# TopLevelBoard.net
KiCad netlist of a schematic drawn in Altium Designer
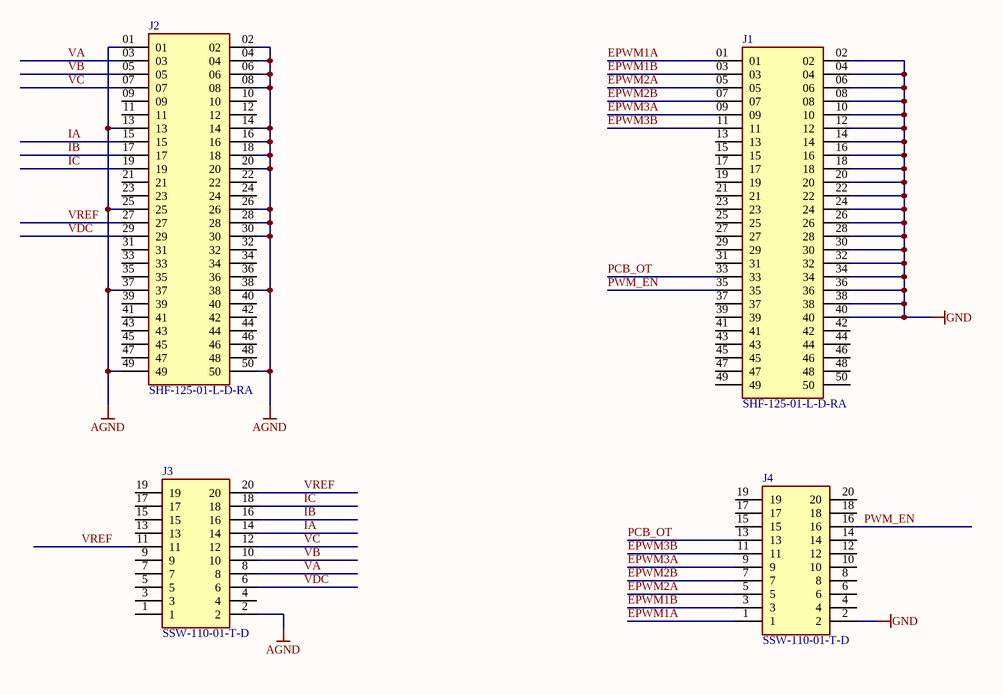
[diagram p0: TopLevelBoard.SchDoc]

(export (version "E")
  (design (tool "Eeschema 10.0.6"))
  (components
    (comp (ref "J1")
      (value "SHF-125-01-L-D-RA")
      (footprint "SAMTEC_SHF-125-01-L-D-RA")
      (fields (field (name "MF") "Samtec"))
      (libsource (lib "FYP_Connectors") (part "SHF-125-01-L-D-RA"))
    )
    (comp (ref "J2")
      (value "SHF-125-01-L-D-RA")
      (footprint "SAMTEC_SHF-125-01-L-D-RA")
      (fields (field (name "MF") "Samtec"))
      (libsource (lib "FYP_Connectors") (part "SHF-125-01-L-D-RA"))
    )
    (comp (ref "J3")
      (value "SSW-110-01-T-D")
      (footprint "SAMTEC_SSW-110-01-T-D")
      (description "Connector")
      (fields (field (name "MOUSER PART NUMBER") "200-SSW11001TD"))
      (libsource (lib "FYP_Connectors") (part "SSW-110-01-T-D"))
    )
    (comp (ref "J4")
      (value "SSW-110-01-T-D")
      (footprint "SAMTEC_SSW-110-01-T-D")
      (description "Connector")
      (fields (field (name "MOUSER PART NUMBER") "200-SSW11001TD"))
      (libsource (lib "FYP_Connectors") (part "SSW-110-01-T-D"))
    )
  )
  (nets
    (net (code "1") (name "/EPWM1A") (class "Default")
      (node (ref "J1") (pin "01") (pinfunction "01_01") (pintype "passive"))
      (node (ref "J4") (pin "1") (pinfunction "1_1") (pintype "passive"))
    )
    (net (code "2") (name "/EPWM1B") (class "Default")
      (node (ref "J1") (pin "03") (pinfunction "03_03") (pintype "passive"))
      (node (ref "J4") (pin "3") (pinfunction "3_3") (pintype "passive"))
    )
    (net (code "3") (name "/EPWM2A") (class "Default")
      (node (ref "J1") (pin "05") (pinfunction "05_05") (pintype "passive"))
      (node (ref "J4") (pin "5") (pinfunction "5_5") (pintype "passive"))
    )
    (net (code "4") (name "/EPWM2B") (class "Default")
      (node (ref "J1") (pin "07") (pinfunction "07_07") (pintype "passive"))
      (node (ref "J4") (pin "7") (pinfunction "7_7") (pintype "passive"))
    )
    (net (code "5") (name "/EPWM3A") (class "Default")
      (node (ref "J1") (pin "09") (pinfunction "09_09") (pintype "passive"))
      (node (ref "J4") (pin "9") (pinfunction "9_9") (pintype "passive"))
    )
    (net (code "6") (name "/EPWM3B") (class "Default")
      (node (ref "J1") (pin "11") (pinfunction "11_11") (pintype "passive"))
      (node (ref "J4") (pin "11") (pinfunction "11_11") (pintype "passive"))
    )
    (net (code "7") (name "/IA") (class "Default")
      (node (ref "J2") (pin "15") (pinfunction "15_15") (pintype "passive"))
      (node (ref "J3") (pin "14") (pinfunction "14_14") (pintype "passive"))
    )
    (net (code "8") (name "/IB") (class "Default")
      (node (ref "J2") (pin "17") (pinfunction "17_17") (pintype "passive"))
      (node (ref "J3") (pin "16") (pinfunction "16_16") (pintype "passive"))
    )
    (net (code "9") (name "/IC") (class "Default")
      (node (ref "J2") (pin "19") (pinfunction "19_19") (pintype "passive"))
      (node (ref "J3") (pin "18") (pinfunction "18_18") (pintype "passive"))
    )
    (net (code "10") (name "/PCB_OT") (class "Default")
      (node (ref "J1") (pin "33") (pinfunction "33_33") (pintype "passive"))
      (node (ref "J4") (pin "13") (pinfunction "13_13") (pintype "passive"))
    )
    (net (code "11") (name "/PWM_EN") (class "Default")
      (node (ref "J1") (pin "35") (pinfunction "35_35") (pintype "passive"))
      (node (ref "J4") (pin "16") (pinfunction "16_16") (pintype "passive"))
    )
    (net (code "12") (name "/VA") (class "Default")
      (node (ref "J2") (pin "03") (pinfunction "03_03") (pintype "passive"))
      (node (ref "J3") (pin "8") (pinfunction "8_8") (pintype "passive"))
    )
    (net (code "13") (name "/VB") (class "Default")
      (node (ref "J2") (pin "05") (pinfunction "05_05") (pintype "passive"))
      (node (ref "J3") (pin "10") (pinfunction "10_10") (pintype "passive"))
    )
    (net (code "14") (name "/VC") (class "Default")
      (node (ref "J2") (pin "07") (pinfunction "07_07") (pintype "passive"))
      (node (ref "J3") (pin "12") (pinfunction "12_12") (pintype "passive"))
    )
    (net (code "15") (name "/VDC") (class "Default")
      (node (ref "J2") (pin "29") (pinfunction "29_29") (pintype "passive"))
      (node (ref "J3") (pin "6") (pinfunction "6_6") (pintype "passive"))
    )
    (net (code "16") (name "/VREF") (class "Default")
      (node (ref "J2") (pin "27") (pinfunction "27_27") (pintype "passive"))
      (node (ref "J3") (pin "11") (pinfunction "11_11") (pintype "passive"))
      (node (ref "J3") (pin "20") (pinfunction "20_20") (pintype "passive"))
    )
    (net (code "17") (name "AGND") (class "Default")
      (node (ref "J2") (pin "01") (pinfunction "01_01") (pintype "passive"))
      (node (ref "J2") (pin "02") (pinfunction "02_02") (pintype "passive"))
      (node (ref "J2") (pin "04") (pinfunction "04_04") (pintype "passive"))
      (node (ref "J2") (pin "06") (pinfunction "06_06") (pintype "passive"))
      (node (ref "J2") (pin "08") (pinfunction "08_08") (pintype "passive"))
      (node (ref "J2") (pin "13") (pinfunction "13_13") (pintype "passive"))
      (node (ref "J2") (pin "14") (pinfunction "14_14") (pintype "passive"))
      (node (ref "J2") (pin "16") (pinfunction "16_16") (pintype "passive"))
      (node (ref "J2") (pin "18") (pinfunction "18_18") (pintype "passive"))
      (node (ref "J2") (pin "20") (pinfunction "20_20") (pintype "passive"))
      (node (ref "J2") (pin "25") (pinfunction "25_25") (pintype "passive"))
      (node (ref "J2") (pin "26") (pinfunction "26_26") (pintype "passive"))
      (node (ref "J2") (pin "28") (pinfunction "28_28") (pintype "passive"))
      (node (ref "J2") (pin "30") (pinfunction "30_30") (pintype "passive"))
      (node (ref "J2") (pin "37") (pinfunction "37_37") (pintype "passive"))
      (node (ref "J2") (pin "38") (pinfunction "38_38") (pintype "passive"))
      (node (ref "J2") (pin "49") (pinfunction "49_49") (pintype "passive"))
      (node (ref "J2") (pin "50") (pinfunction "50_50") (pintype "passive"))
      (node (ref "J3") (pin "2") (pinfunction "2_2") (pintype "passive"))
    )
    (net (code "18") (name "GND") (class "Default")
      (node (ref "J1") (pin "02") (pinfunction "02_02") (pintype "passive"))
      (node (ref "J1") (pin "04") (pinfunction "04_04") (pintype "passive"))
      (node (ref "J1") (pin "06") (pinfunction "06_06") (pintype "passive"))
      (node (ref "J1") (pin "08") (pinfunction "08_08") (pintype "passive"))
      (node (ref "J1") (pin "10") (pinfunction "10_10") (pintype "passive"))
      (node (ref "J1") (pin "12") (pinfunction "12_12") (pintype "passive"))
      (node (ref "J1") (pin "14") (pinfunction "14_14") (pintype "passive"))
      (node (ref "J1") (pin "16") (pinfunction "16_16") (pintype "passive"))
      (node (ref "J1") (pin "18") (pinfunction "18_18") (pintype "passive"))
      (node (ref "J1") (pin "20") (pinfunction "20_20") (pintype "passive"))
      (node (ref "J1") (pin "22") (pinfunction "22_22") (pintype "passive"))
      (node (ref "J1") (pin "24") (pinfunction "24_24") (pintype "passive"))
      (node (ref "J1") (pin "26") (pinfunction "26_26") (pintype "passive"))
      (node (ref "J1") (pin "28") (pinfunction "28_28") (pintype "passive"))
      (node (ref "J1") (pin "30") (pinfunction "30_30") (pintype "passive"))
      (node (ref "J1") (pin "32") (pinfunction "32_32") (pintype "passive"))
      (node (ref "J1") (pin "34") (pinfunction "34_34") (pintype "passive"))
      (node (ref "J1") (pin "36") (pinfunction "36_36") (pintype "passive"))
      (node (ref "J1") (pin "38") (pinfunction "38_38") (pintype "passive"))
      (node (ref "J1") (pin "40") (pinfunction "40_40") (pintype "passive"))
      (node (ref "J4") (pin "2") (pinfunction "2_2") (pintype "passive"))
    )
    (net (code "19") (name "unconnected-(J1-Pad13)") (class "Default")
      (node (ref "J1") (pin "13") (pinfunction "13_13") (pintype "passive"))
    )
    (net (code "20") (name "unconnected-(J1-Pad15)") (class "Default")
      (node (ref "J1") (pin "15") (pinfunction "15_15") (pintype "passive"))
    )
    (net (code "21") (name "unconnected-(J1-Pad17)") (class "Default")
      (node (ref "J1") (pin "17") (pinfunction "17_17") (pintype "passive"))
    )
    (net (code "22") (name "unconnected-(J1-Pad19)") (class "Default")
      (node (ref "J1") (pin "19") (pinfunction "19_19") (pintype "passive"))
    )
    (net (code "23") (name "unconnected-(J1-Pad21)") (class "Default")
      (node (ref "J1") (pin "21") (pinfunction "21_21") (pintype "passive"))
    )
    (net (code "24") (name "unconnected-(J1-Pad23)") (class "Default")
      (node (ref "J1") (pin "23") (pinfunction "23_23") (pintype "passive"))
    )
    (net (code "25") (name "unconnected-(J1-Pad25)") (class "Default")
      (node (ref "J1") (pin "25") (pinfunction "25_25") (pintype "passive"))
    )
    (net (code "26") (name "unconnected-(J1-Pad27)") (class "Default")
      (node (ref "J1") (pin "27") (pinfunction "27_27") (pintype "passive"))
    )
    (net (code "27") (name "unconnected-(J1-Pad29)") (class "Default")
      (node (ref "J1") (pin "29") (pinfunction "29_29") (pintype "passive"))
    )
    (net (code "28") (name "unconnected-(J1-Pad31)") (class "Default")
      (node (ref "J1") (pin "31") (pinfunction "31_31") (pintype "passive"))
    )
    (net (code "29") (name "unconnected-(J1-Pad37)") (class "Default")
      (node (ref "J1") (pin "37") (pinfunction "37_37") (pintype "passive"))
    )
    (net (code "30") (name "unconnected-(J1-Pad39)") (class "Default")
      (node (ref "J1") (pin "39") (pinfunction "39_39") (pintype "passive"))
    )
    (net (code "31") (name "unconnected-(J1-Pad41)") (class "Default")
      (node (ref "J1") (pin "41") (pinfunction "41_41") (pintype "passive"))
    )
    (net (code "32") (name "unconnected-(J1-Pad42)") (class "Default")
      (node (ref "J1") (pin "42") (pinfunction "42_42") (pintype "passive"))
    )
    (net (code "33") (name "unconnected-(J1-Pad43)") (class "Default")
      (node (ref "J1") (pin "43") (pinfunction "43_43") (pintype "passive"))
    )
    (net (code "34") (name "unconnected-(J1-Pad44)") (class "Default")
      (node (ref "J1") (pin "44") (pinfunction "44_44") (pintype "passive"))
    )
    (net (code "35") (name "unconnected-(J1-Pad45)") (class "Default")
      (node (ref "J1") (pin "45") (pinfunction "45_45") (pintype "passive"))
    )
    (net (code "36") (name "unconnected-(J1-Pad46)") (class "Default")
      (node (ref "J1") (pin "46") (pinfunction "46_46") (pintype "passive"))
    )
    (net (code "37") (name "unconnected-(J1-Pad47)") (class "Default")
      (node (ref "J1") (pin "47") (pinfunction "47_47") (pintype "passive"))
    )
    (net (code "38") (name "unconnected-(J1-Pad48)") (class "Default")
      (node (ref "J1") (pin "48") (pinfunction "48_48") (pintype "passive"))
    )
    (net (code "39") (name "unconnected-(J1-Pad49)") (class "Default")
      (node (ref "J1") (pin "49") (pinfunction "49_49") (pintype "passive"))
    )
    (net (code "40") (name "unconnected-(J1-Pad50)") (class "Default")
      (node (ref "J1") (pin "50") (pinfunction "50_50") (pintype "passive"))
    )
    (net (code "41") (name "unconnected-(J2-Pad09)") (class "Default")
      (node (ref "J2") (pin "09") (pinfunction "09_09") (pintype "passive"))
    )
    (net (code "42") (name "unconnected-(J2-Pad10)") (class "Default")
      (node (ref "J2") (pin "10") (pinfunction "10_10") (pintype "passive"))
    )
    (net (code "43") (name "unconnected-(J2-Pad11)") (class "Default")
      (node (ref "J2") (pin "11") (pinfunction "11_11") (pintype "passive"))
    )
    (net (code "44") (name "unconnected-(J2-Pad12)") (class "Default")
      (node (ref "J2") (pin "12") (pinfunction "12_12") (pintype "passive"))
    )
    (net (code "45") (name "unconnected-(J2-Pad21)") (class "Default")
      (node (ref "J2") (pin "21") (pinfunction "21_21") (pintype "passive"))
    )
    (net (code "46") (name "unconnected-(J2-Pad22)") (class "Default")
      (node (ref "J2") (pin "22") (pinfunction "22_22") (pintype "passive"))
    )
    (net (code "47") (name "unconnected-(J2-Pad23)") (class "Default")
      (node (ref "J2") (pin "23") (pinfunction "23_23") (pintype "passive"))
    )
    (net (code "48") (name "unconnected-(J2-Pad24)") (class "Default")
      (node (ref "J2") (pin "24") (pinfunction "24_24") (pintype "passive"))
    )
    (net (code "49") (name "unconnected-(J2-Pad31)") (class "Default")
      (node (ref "J2") (pin "31") (pinfunction "31_31") (pintype "passive"))
    )
    (net (code "50") (name "unconnected-(J2-Pad32)") (class "Default")
      (node (ref "J2") (pin "32") (pinfunction "32_32") (pintype "passive"))
    )
    (net (code "51") (name "unconnected-(J2-Pad33)") (class "Default")
      (node (ref "J2") (pin "33") (pinfunction "33_33") (pintype "passive"))
    )
    (net (code "52") (name "unconnected-(J2-Pad34)") (class "Default")
      (node (ref "J2") (pin "34") (pinfunction "34_34") (pintype "passive"))
    )
    (net (code "53") (name "unconnected-(J2-Pad35)") (class "Default")
      (node (ref "J2") (pin "35") (pinfunction "35_35") (pintype "passive"))
    )
    (net (code "54") (name "unconnected-(J2-Pad36)") (class "Default")
      (node (ref "J2") (pin "36") (pinfunction "36_36") (pintype "passive"))
    )
    (net (code "55") (name "unconnected-(J2-Pad39)") (class "Default")
      (node (ref "J2") (pin "39") (pinfunction "39_39") (pintype "passive"))
    )
    (net (code "56") (name "unconnected-(J2-Pad40)") (class "Default")
      (node (ref "J2") (pin "40") (pinfunction "40_40") (pintype "passive"))
    )
    (net (code "57") (name "unconnected-(J2-Pad41)") (class "Default")
      (node (ref "J2") (pin "41") (pinfunction "41_41") (pintype "passive"))
    )
    (net (code "58") (name "unconnected-(J2-Pad42)") (class "Default")
      (node (ref "J2") (pin "42") (pinfunction "42_42") (pintype "passive"))
    )
    (net (code "59") (name "unconnected-(J2-Pad43)") (class "Default")
      (node (ref "J2") (pin "43") (pinfunction "43_43") (pintype "passive"))
    )
    (net (code "60") (name "unconnected-(J2-Pad44)") (class "Default")
      (node (ref "J2") (pin "44") (pinfunction "44_44") (pintype "passive"))
    )
    (net (code "61") (name "unconnected-(J2-Pad45)") (class "Default")
      (node (ref "J2") (pin "45") (pinfunction "45_45") (pintype "passive"))
    )
    (net (code "62") (name "unconnected-(J2-Pad46)") (class "Default")
      (node (ref "J2") (pin "46") (pinfunction "46_46") (pintype "passive"))
    )
    (net (code "63") (name "unconnected-(J2-Pad47)") (class "Default")
      (node (ref "J2") (pin "47") (pinfunction "47_47") (pintype "passive"))
    )
    (net (code "64") (name "unconnected-(J2-Pad48)") (class "Default")
      (node (ref "J2") (pin "48") (pinfunction "48_48") (pintype "passive"))
    )
    (net (code "65") (name "unconnected-(J3-Pad1)") (class "Default")
      (node (ref "J3") (pin "1") (pinfunction "1_1") (pintype "passive"))
    )
    (net (code "66") (name "unconnected-(J3-Pad3)") (class "Default")
      (node (ref "J3") (pin "3") (pinfunction "3_3") (pintype "passive"))
    )
    (net (code "67") (name "unconnected-(J3-Pad4)") (class "Default")
      (node (ref "J3") (pin "4") (pinfunction "4_4") (pintype "passive"))
    )
    (net (code "68") (name "unconnected-(J3-Pad5)") (class "Default")
      (node (ref "J3") (pin "5") (pinfunction "5_5") (pintype "passive"))
    )
    (net (code "69") (name "unconnected-(J3-Pad7)") (class "Default")
      (node (ref "J3") (pin "7") (pinfunction "7_7") (pintype "passive"))
    )
    (net (code "70") (name "unconnected-(J3-Pad9)") (class "Default")
      (node (ref "J3") (pin "9") (pinfunction "9_9") (pintype "passive"))
    )
    (net (code "71") (name "unconnected-(J3-Pad13)") (class "Default")
      (node (ref "J3") (pin "13") (pinfunction "13_13") (pintype "passive"))
    )
    (net (code "72") (name "unconnected-(J3-Pad15)") (class "Default")
      (node (ref "J3") (pin "15") (pinfunction "15_15") (pintype "passive"))
    )
    (net (code "73") (name "unconnected-(J3-Pad17)") (class "Default")
      (node (ref "J3") (pin "17") (pinfunction "17_17") (pintype "passive"))
    )
    (net (code "74") (name "unconnected-(J3-Pad19)") (class "Default")
      (node (ref "J3") (pin "19") (pinfunction "19_19") (pintype "passive"))
    )
    (net (code "75") (name "unconnected-(J4-Pad4)") (class "Default")
      (node (ref "J4") (pin "4") (pinfunction "4_4") (pintype "passive"))
    )
    (net (code "76") (name "unconnected-(J4-Pad6)") (class "Default")
      (node (ref "J4") (pin "6") (pinfunction "6_6") (pintype "passive"))
    )
    (net (code "77") (name "unconnected-(J4-Pad8)") (class "Default")
      (node (ref "J4") (pin "8") (pinfunction "8_8") (pintype "passive"))
    )
    (net (code "78") (name "unconnected-(J4-Pad10)") (class "Default")
      (node (ref "J4") (pin "10") (pinfunction "10_10") (pintype "passive"))
    )
    (net (code "79") (name "unconnected-(J4-Pad12)") (class "Default")
      (node (ref "J4") (pin "12") (pinfunction "12_12") (pintype "passive"))
    )
    (net (code "80") (name "unconnected-(J4-Pad14)") (class "Default")
      (node (ref "J4") (pin "14") (pinfunction "14_14") (pintype "passive"))
    )
    (net (code "81") (name "unconnected-(J4-Pad15)") (class "Default")
      (node (ref "J4") (pin "15") (pinfunction "15_15") (pintype "passive"))
    )
    (net (code "82") (name "unconnected-(J4-Pad17)") (class "Default")
      (node (ref "J4") (pin "17") (pinfunction "17_17") (pintype "passive"))
    )
    (net (code "83") (name "unconnected-(J4-Pad18)") (class "Default")
      (node (ref "J4") (pin "18") (pinfunction "18_18") (pintype "passive"))
    )
    (net (code "84") (name "unconnected-(J4-Pad19)") (class "Default")
      (node (ref "J4") (pin "19") (pinfunction "19_19") (pintype "passive"))
    )
    (net (code "85") (name "unconnected-(J4-Pad20)") (class "Default")
      (node (ref "J4") (pin "20") (pinfunction "20_20") (pintype "passive"))
    )
  )
)
